# RC_Filters_MicroD.net
KiCad netlist of a schematic drawn in Altium Designer
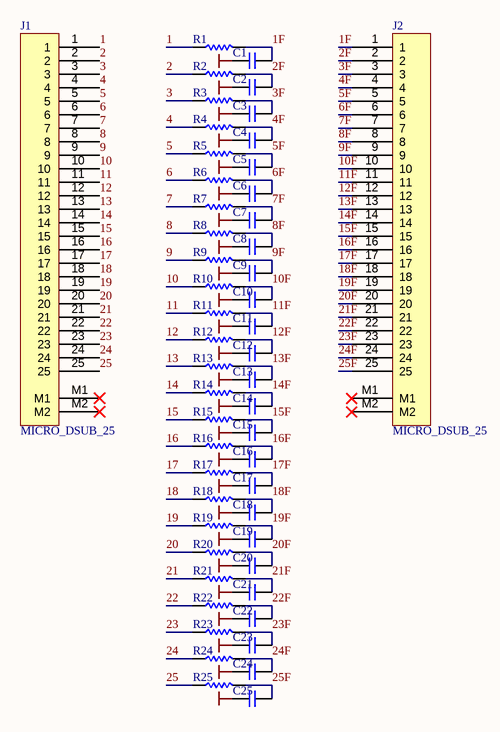
[diagram p0: RC_Filters_MicroD.SchDoc]

(export (version "E")
  (design (tool "Eeschema 10.0.6"))
  (components
    (comp (ref "C1") (value "Capacitor") (footprint "C0402") (libsource (lib "Passives") (part "Capacitor")))
    (comp (ref "C2") (value "Capacitor") (footprint "C0402") (libsource (lib "Passives") (part "Capacitor")))
    (comp (ref "C3") (value "Capacitor") (footprint "C0402") (libsource (lib "Passives") (part "Capacitor")))
    (comp (ref "C4") (value "Capacitor") (footprint "C0402") (libsource (lib "Passives") (part "Capacitor")))
    (comp (ref "C5") (value "Capacitor") (footprint "C0402") (libsource (lib "Passives") (part "Capacitor")))
    (comp (ref "C6") (value "Capacitor") (footprint "C0402") (libsource (lib "Passives") (part "Capacitor")))
    (comp (ref "C7") (value "Capacitor") (footprint "C0402") (libsource (lib "Passives") (part "Capacitor")))
    (comp (ref "C8") (value "Capacitor") (footprint "C0402") (libsource (lib "Passives") (part "Capacitor")))
    (comp (ref "C9") (value "Capacitor") (footprint "C0402") (libsource (lib "Passives") (part "Capacitor")))
    (comp (ref "C10") (value "Capacitor") (footprint "C0402") (libsource (lib "Passives") (part "Capacitor")))
    (comp (ref "C11") (value "Capacitor") (footprint "C0402") (libsource (lib "Passives") (part "Capacitor")))
    (comp (ref "C12") (value "Capacitor") (footprint "C0402") (libsource (lib "Passives") (part "Capacitor")))
    (comp (ref "C13") (value "Capacitor") (footprint "C0402") (libsource (lib "Passives") (part "Capacitor")))
    (comp (ref "C14") (value "Capacitor") (footprint "C0402") (libsource (lib "Passives") (part "Capacitor")))
    (comp (ref "C15") (value "Capacitor") (footprint "C0402") (libsource (lib "Passives") (part "Capacitor")))
    (comp (ref "C16") (value "Capacitor") (footprint "C0402") (libsource (lib "Passives") (part "Capacitor")))
    (comp (ref "C17") (value "Capacitor") (footprint "C0402") (libsource (lib "Passives") (part "Capacitor")))
    (comp (ref "C18") (value "Capacitor") (footprint "C0402") (libsource (lib "Passives") (part "Capacitor")))
    (comp (ref "C19") (value "Capacitor") (footprint "C0402") (libsource (lib "Passives") (part "Capacitor")))
    (comp (ref "C20") (value "Capacitor") (footprint "C0402") (libsource (lib "Passives") (part "Capacitor")))
    (comp (ref "C21") (value "Capacitor") (footprint "C0402") (libsource (lib "Passives") (part "Capacitor")))
    (comp (ref "C22") (value "Capacitor") (footprint "C0402") (libsource (lib "Passives") (part "Capacitor")))
    (comp (ref "C23") (value "Capacitor") (footprint "C0402") (libsource (lib "Passives") (part "Capacitor")))
    (comp (ref "C24") (value "Capacitor") (footprint "C0402") (libsource (lib "Passives") (part "Capacitor")))
    (comp (ref "C25") (value "Capacitor") (footprint "C0402") (libsource (lib "Passives") (part "Capacitor")))
    (comp (ref "J1")
      (value "MICRO_DSUB_25")
      (footprint "581-M25-113L461")
      (description "Micro D-Sub 25 pin connector")
      (libsource (lib "") (part "MICRO_DSUB_25_1"))
    )
    (comp (ref "J2")
      (value "MICRO_DSUB_25")
      (footprint "581-M25-213L461")
      (description "Micro D-Sub 25 pin connector")
      (libsource (lib "Connectors") (part "MICRO_DSUB_25"))
    )
    (comp (ref "R1") (value "Resistor") (footprint "R0402") (libsource (lib "Passives") (part "Resistor")))
    (comp (ref "R2") (value "Resistor") (footprint "R0402") (libsource (lib "Passives") (part "Resistor")))
    (comp (ref "R3") (value "Resistor") (footprint "R0402") (libsource (lib "Passives") (part "Resistor")))
    (comp (ref "R4") (value "Resistor") (footprint "R0402") (libsource (lib "Passives") (part "Resistor")))
    (comp (ref "R5") (value "Resistor") (footprint "R0402") (libsource (lib "Passives") (part "Resistor")))
    (comp (ref "R6") (value "Resistor") (footprint "R0402") (libsource (lib "Passives") (part "Resistor")))
    (comp (ref "R7") (value "Resistor") (footprint "R0402") (libsource (lib "Passives") (part "Resistor")))
    (comp (ref "R8") (value "Resistor") (footprint "R0402") (libsource (lib "Passives") (part "Resistor")))
    (comp (ref "R9") (value "Resistor") (footprint "R0402") (libsource (lib "Passives") (part "Resistor")))
    (comp (ref "R10") (value "Resistor") (footprint "R0402") (libsource (lib "Passives") (part "Resistor")))
    (comp (ref "R11") (value "Resistor") (footprint "R0402") (libsource (lib "Passives") (part "Resistor")))
    (comp (ref "R12") (value "Resistor") (footprint "R0402") (libsource (lib "Passives") (part "Resistor")))
    (comp (ref "R13") (value "Resistor") (footprint "R0402") (libsource (lib "Passives") (part "Resistor")))
    (comp (ref "R14") (value "Resistor") (footprint "R0402") (libsource (lib "Passives") (part "Resistor")))
    (comp (ref "R15") (value "Resistor") (footprint "R0402") (libsource (lib "Passives") (part "Resistor")))
    (comp (ref "R16") (value "Resistor") (footprint "R0402") (libsource (lib "Passives") (part "Resistor")))
    (comp (ref "R17") (value "Resistor") (footprint "R0402") (libsource (lib "Passives") (part "Resistor")))
    (comp (ref "R18") (value "Resistor") (footprint "R0402") (libsource (lib "Passives") (part "Resistor")))
    (comp (ref "R19") (value "Resistor") (footprint "R0402") (libsource (lib "Passives") (part "Resistor")))
    (comp (ref "R20") (value "Resistor") (footprint "R0402") (libsource (lib "Passives") (part "Resistor")))
    (comp (ref "R21") (value "Resistor") (footprint "R0402") (libsource (lib "Passives") (part "Resistor")))
    (comp (ref "R22") (value "Resistor") (footprint "R0402") (libsource (lib "Passives") (part "Resistor")))
    (comp (ref "R23") (value "Resistor") (footprint "R0402") (libsource (lib "Passives") (part "Resistor")))
    (comp (ref "R24") (value "Resistor") (footprint "R0402") (libsource (lib "Passives") (part "Resistor")))
    (comp (ref "R25") (value "Resistor") (footprint "R0402") (libsource (lib "Passives") (part "Resistor")))
  )
  (nets
    (net (code "1") (name "/1") (class "Default")
      (node (ref "J1") (pin "1") (pinfunction "1_1") (pintype "passive"))
      (node (ref "R1") (pin "0") (pinfunction "0_0") (pintype "passive"))
    )
    (net (code "2") (name "/1F") (class "Default")
      (node (ref "C1") (pin "1") (pinfunction "1_1") (pintype "passive"))
      (node (ref "J2") (pin "1") (pinfunction "1_1") (pintype "passive"))
      (node (ref "R1") (pin "1") (pinfunction "1_1") (pintype "passive"))
    )
    (net (code "3") (name "/2") (class "Default")
      (node (ref "J1") (pin "2") (pinfunction "2_2") (pintype "passive"))
      (node (ref "R2") (pin "0") (pinfunction "0_0") (pintype "passive"))
    )
    (net (code "4") (name "/2F") (class "Default")
      (node (ref "C2") (pin "1") (pinfunction "1_1") (pintype "passive"))
      (node (ref "J2") (pin "2") (pinfunction "2_2") (pintype "passive"))
      (node (ref "R2") (pin "1") (pinfunction "1_1") (pintype "passive"))
    )
    (net (code "5") (name "/3") (class "Default")
      (node (ref "J1") (pin "3") (pinfunction "3_3") (pintype "passive"))
      (node (ref "R3") (pin "0") (pinfunction "0_0") (pintype "passive"))
    )
    (net (code "6") (name "/3F") (class "Default")
      (node (ref "C3") (pin "1") (pinfunction "1_1") (pintype "passive"))
      (node (ref "J2") (pin "3") (pinfunction "3_3") (pintype "passive"))
      (node (ref "R3") (pin "1") (pinfunction "1_1") (pintype "passive"))
    )
    (net (code "7") (name "/4") (class "Default")
      (node (ref "J1") (pin "4") (pinfunction "4_4") (pintype "passive"))
      (node (ref "R4") (pin "0") (pinfunction "0_0") (pintype "passive"))
    )
    (net (code "8") (name "/4F") (class "Default")
      (node (ref "C4") (pin "1") (pinfunction "1_1") (pintype "passive"))
      (node (ref "J2") (pin "4") (pinfunction "4_4") (pintype "passive"))
      (node (ref "R4") (pin "1") (pinfunction "1_1") (pintype "passive"))
    )
    (net (code "9") (name "/5") (class "Default")
      (node (ref "J1") (pin "5") (pinfunction "5_5") (pintype "passive"))
      (node (ref "R5") (pin "0") (pinfunction "0_0") (pintype "passive"))
    )
    (net (code "10") (name "/5F") (class "Default")
      (node (ref "C5") (pin "1") (pinfunction "1_1") (pintype "passive"))
      (node (ref "J2") (pin "5") (pinfunction "5_5") (pintype "passive"))
      (node (ref "R5") (pin "1") (pinfunction "1_1") (pintype "passive"))
    )
    (net (code "11") (name "/6") (class "Default")
      (node (ref "J1") (pin "6") (pinfunction "6_6") (pintype "passive"))
      (node (ref "R6") (pin "0") (pinfunction "0_0") (pintype "passive"))
    )
    (net (code "12") (name "/6F") (class "Default")
      (node (ref "C6") (pin "1") (pinfunction "1_1") (pintype "passive"))
      (node (ref "J2") (pin "6") (pinfunction "6_6") (pintype "passive"))
      (node (ref "R6") (pin "1") (pinfunction "1_1") (pintype "passive"))
    )
    (net (code "13") (name "/7") (class "Default")
      (node (ref "J1") (pin "7") (pinfunction "7_7") (pintype "passive"))
      (node (ref "R7") (pin "0") (pinfunction "0_0") (pintype "passive"))
    )
    (net (code "14") (name "/7F") (class "Default")
      (node (ref "C7") (pin "1") (pinfunction "1_1") (pintype "passive"))
      (node (ref "J2") (pin "7") (pinfunction "7_7") (pintype "passive"))
      (node (ref "R7") (pin "1") (pinfunction "1_1") (pintype "passive"))
    )
    (net (code "15") (name "/8") (class "Default")
      (node (ref "J1") (pin "8") (pinfunction "8_8") (pintype "passive"))
      (node (ref "R8") (pin "0") (pinfunction "0_0") (pintype "passive"))
    )
    (net (code "16") (name "/8F") (class "Default")
      (node (ref "C8") (pin "1") (pinfunction "1_1") (pintype "passive"))
      (node (ref "J2") (pin "8") (pinfunction "8_8") (pintype "passive"))
      (node (ref "R8") (pin "1") (pinfunction "1_1") (pintype "passive"))
    )
    (net (code "17") (name "/9") (class "Default")
      (node (ref "J1") (pin "9") (pinfunction "9_9") (pintype "passive"))
      (node (ref "R9") (pin "0") (pinfunction "0_0") (pintype "passive"))
    )
    (net (code "18") (name "/9F") (class "Default")
      (node (ref "C9") (pin "1") (pinfunction "1_1") (pintype "passive"))
      (node (ref "J2") (pin "9") (pinfunction "9_9") (pintype "passive"))
      (node (ref "R9") (pin "1") (pinfunction "1_1") (pintype "passive"))
    )
    (net (code "19") (name "/10") (class "Default")
      (node (ref "J1") (pin "10") (pinfunction "10_10") (pintype "passive"))
      (node (ref "R10") (pin "0") (pinfunction "0_0") (pintype "passive"))
    )
    (net (code "20") (name "/10F") (class "Default")
      (node (ref "C10") (pin "1") (pinfunction "1_1") (pintype "passive"))
      (node (ref "J2") (pin "10") (pinfunction "10_10") (pintype "passive"))
      (node (ref "R10") (pin "1") (pinfunction "1_1") (pintype "passive"))
    )
    (net (code "21") (name "/11") (class "Default")
      (node (ref "J1") (pin "11") (pinfunction "11_11") (pintype "passive"))
      (node (ref "R11") (pin "0") (pinfunction "0_0") (pintype "passive"))
    )
    (net (code "22") (name "/11F") (class "Default")
      (node (ref "C11") (pin "1") (pinfunction "1_1") (pintype "passive"))
      (node (ref "J2") (pin "11") (pinfunction "11_11") (pintype "passive"))
      (node (ref "R11") (pin "1") (pinfunction "1_1") (pintype "passive"))
    )
    (net (code "23") (name "/12") (class "Default")
      (node (ref "J1") (pin "12") (pinfunction "12_12") (pintype "passive"))
      (node (ref "R12") (pin "0") (pinfunction "0_0") (pintype "passive"))
    )
    (net (code "24") (name "/12F") (class "Default")
      (node (ref "C12") (pin "1") (pinfunction "1_1") (pintype "passive"))
      (node (ref "J2") (pin "12") (pinfunction "12_12") (pintype "passive"))
      (node (ref "R12") (pin "1") (pinfunction "1_1") (pintype "passive"))
    )
    (net (code "25") (name "/13") (class "Default")
      (node (ref "J1") (pin "13") (pinfunction "13_13") (pintype "passive"))
      (node (ref "R13") (pin "0") (pinfunction "0_0") (pintype "passive"))
    )
    (net (code "26") (name "/13F") (class "Default")
      (node (ref "C13") (pin "1") (pinfunction "1_1") (pintype "passive"))
      (node (ref "J2") (pin "13") (pinfunction "13_13") (pintype "passive"))
      (node (ref "R13") (pin "1") (pinfunction "1_1") (pintype "passive"))
    )
    (net (code "27") (name "/14") (class "Default")
      (node (ref "J1") (pin "14") (pinfunction "14_14") (pintype "passive"))
      (node (ref "R14") (pin "0") (pinfunction "0_0") (pintype "passive"))
    )
    (net (code "28") (name "/14F") (class "Default")
      (node (ref "C14") (pin "1") (pinfunction "1_1") (pintype "passive"))
      (node (ref "J2") (pin "14") (pinfunction "14_14") (pintype "passive"))
      (node (ref "R14") (pin "1") (pinfunction "1_1") (pintype "passive"))
    )
    (net (code "29") (name "/15") (class "Default")
      (node (ref "J1") (pin "15") (pinfunction "15_15") (pintype "passive"))
      (node (ref "R15") (pin "0") (pinfunction "0_0") (pintype "passive"))
    )
    (net (code "30") (name "/15F") (class "Default")
      (node (ref "C15") (pin "1") (pinfunction "1_1") (pintype "passive"))
      (node (ref "J2") (pin "15") (pinfunction "15_15") (pintype "passive"))
      (node (ref "R15") (pin "1") (pinfunction "1_1") (pintype "passive"))
    )
    (net (code "31") (name "/16") (class "Default")
      (node (ref "J1") (pin "16") (pinfunction "16_16") (pintype "passive"))
      (node (ref "R16") (pin "0") (pinfunction "0_0") (pintype "passive"))
    )
    (net (code "32") (name "/16F") (class "Default")
      (node (ref "C16") (pin "1") (pinfunction "1_1") (pintype "passive"))
      (node (ref "J2") (pin "16") (pinfunction "16_16") (pintype "passive"))
      (node (ref "R16") (pin "1") (pinfunction "1_1") (pintype "passive"))
    )
    (net (code "33") (name "/17") (class "Default")
      (node (ref "J1") (pin "17") (pinfunction "17_17") (pintype "passive"))
      (node (ref "R17") (pin "0") (pinfunction "0_0") (pintype "passive"))
    )
    (net (code "34") (name "/17F") (class "Default")
      (node (ref "C17") (pin "1") (pinfunction "1_1") (pintype "passive"))
      (node (ref "J2") (pin "17") (pinfunction "17_17") (pintype "passive"))
      (node (ref "R17") (pin "1") (pinfunction "1_1") (pintype "passive"))
    )
    (net (code "35") (name "/18") (class "Default")
      (node (ref "J1") (pin "18") (pinfunction "18_18") (pintype "passive"))
      (node (ref "R18") (pin "0") (pinfunction "0_0") (pintype "passive"))
    )
    (net (code "36") (name "/18F") (class "Default")
      (node (ref "C18") (pin "1") (pinfunction "1_1") (pintype "passive"))
      (node (ref "J2") (pin "18") (pinfunction "18_18") (pintype "passive"))
      (node (ref "R18") (pin "1") (pinfunction "1_1") (pintype "passive"))
    )
    (net (code "37") (name "/19") (class "Default")
      (node (ref "J1") (pin "19") (pinfunction "19_19") (pintype "passive"))
      (node (ref "R19") (pin "0") (pinfunction "0_0") (pintype "passive"))
    )
    (net (code "38") (name "/19F") (class "Default")
      (node (ref "C19") (pin "1") (pinfunction "1_1") (pintype "passive"))
      (node (ref "J2") (pin "19") (pinfunction "19_19") (pintype "passive"))
      (node (ref "R19") (pin "1") (pinfunction "1_1") (pintype "passive"))
    )
    (net (code "39") (name "/20") (class "Default")
      (node (ref "J1") (pin "20") (pinfunction "20_20") (pintype "passive"))
      (node (ref "R20") (pin "0") (pinfunction "0_0") (pintype "passive"))
    )
    (net (code "40") (name "/20F") (class "Default")
      (node (ref "C20") (pin "1") (pinfunction "1_1") (pintype "passive"))
      (node (ref "J2") (pin "20") (pinfunction "20_20") (pintype "passive"))
      (node (ref "R20") (pin "1") (pinfunction "1_1") (pintype "passive"))
    )
    (net (code "41") (name "/21") (class "Default")
      (node (ref "J1") (pin "21") (pinfunction "21_21") (pintype "passive"))
      (node (ref "R21") (pin "0") (pinfunction "0_0") (pintype "passive"))
    )
    (net (code "42") (name "/21F") (class "Default")
      (node (ref "C21") (pin "1") (pinfunction "1_1") (pintype "passive"))
      (node (ref "J2") (pin "21") (pinfunction "21_21") (pintype "passive"))
      (node (ref "R21") (pin "1") (pinfunction "1_1") (pintype "passive"))
    )
    (net (code "43") (name "/22") (class "Default")
      (node (ref "J1") (pin "22") (pinfunction "22_22") (pintype "passive"))
      (node (ref "R22") (pin "0") (pinfunction "0_0") (pintype "passive"))
    )
    (net (code "44") (name "/22F") (class "Default")
      (node (ref "C22") (pin "1") (pinfunction "1_1") (pintype "passive"))
      (node (ref "J2") (pin "22") (pinfunction "22_22") (pintype "passive"))
      (node (ref "R22") (pin "1") (pinfunction "1_1") (pintype "passive"))
    )
    (net (code "45") (name "/23") (class "Default")
      (node (ref "J1") (pin "23") (pinfunction "23_23") (pintype "passive"))
      (node (ref "R23") (pin "0") (pinfunction "0_0") (pintype "passive"))
    )
    (net (code "46") (name "/23F") (class "Default")
      (node (ref "C23") (pin "1") (pinfunction "1_1") (pintype "passive"))
      (node (ref "J2") (pin "23") (pinfunction "23_23") (pintype "passive"))
      (node (ref "R23") (pin "1") (pinfunction "1_1") (pintype "passive"))
    )
    (net (code "47") (name "/24") (class "Default")
      (node (ref "J1") (pin "24") (pinfunction "24_24") (pintype "passive"))
      (node (ref "R24") (pin "0") (pinfunction "0_0") (pintype "passive"))
    )
    (net (code "48") (name "/24F") (class "Default")
      (node (ref "C24") (pin "1") (pinfunction "1_1") (pintype "passive"))
      (node (ref "J2") (pin "24") (pinfunction "24_24") (pintype "passive"))
      (node (ref "R24") (pin "1") (pinfunction "1_1") (pintype "passive"))
    )
    (net (code "49") (name "/25") (class "Default")
      (node (ref "J1") (pin "25") (pinfunction "25_25") (pintype "passive"))
      (node (ref "R25") (pin "0") (pinfunction "0_0") (pintype "passive"))
    )
    (net (code "50") (name "/25F") (class "Default")
      (node (ref "C25") (pin "1") (pinfunction "1_1") (pintype "passive"))
      (node (ref "J2") (pin "25") (pinfunction "25_25") (pintype "passive"))
      (node (ref "R25") (pin "1") (pinfunction "1_1") (pintype "passive"))
    )
    (net (code "51") (name "COM") (class "Default")
      (node (ref "C1") (pin "0") (pinfunction "0_0") (pintype "passive"))
      (node (ref "C10") (pin "0") (pinfunction "0_0") (pintype "passive"))
      (node (ref "C11") (pin "0") (pinfunction "0_0") (pintype "passive"))
      (node (ref "C12") (pin "0") (pinfunction "0_0") (pintype "passive"))
      (node (ref "C13") (pin "0") (pinfunction "0_0") (pintype "passive"))
      (node (ref "C14") (pin "0") (pinfunction "0_0") (pintype "passive"))
      (node (ref "C15") (pin "0") (pinfunction "0_0") (pintype "passive"))
      (node (ref "C16") (pin "0") (pinfunction "0_0") (pintype "passive"))
      (node (ref "C17") (pin "0") (pinfunction "0_0") (pintype "passive"))
      (node (ref "C18") (pin "0") (pinfunction "0_0") (pintype "passive"))
      (node (ref "C19") (pin "0") (pinfunction "0_0") (pintype "passive"))
      (node (ref "C2") (pin "0") (pinfunction "0_0") (pintype "passive"))
      (node (ref "C20") (pin "0") (pinfunction "0_0") (pintype "passive"))
      (node (ref "C21") (pin "0") (pinfunction "0_0") (pintype "passive"))
      (node (ref "C22") (pin "0") (pinfunction "0_0") (pintype "passive"))
      (node (ref "C23") (pin "0") (pinfunction "0_0") (pintype "passive"))
      (node (ref "C24") (pin "0") (pinfunction "0_0") (pintype "passive"))
      (node (ref "C25") (pin "0") (pinfunction "0_0") (pintype "passive"))
      (node (ref "C3") (pin "0") (pinfunction "0_0") (pintype "passive"))
      (node (ref "C4") (pin "0") (pinfunction "0_0") (pintype "passive"))
      (node (ref "C5") (pin "0") (pinfunction "0_0") (pintype "passive"))
      (node (ref "C6") (pin "0") (pinfunction "0_0") (pintype "passive"))
      (node (ref "C7") (pin "0") (pinfunction "0_0") (pintype "passive"))
      (node (ref "C8") (pin "0") (pinfunction "0_0") (pintype "passive"))
      (node (ref "C9") (pin "0") (pinfunction "0_0") (pintype "passive"))
    )
    (net (code "52") (name "unconnected-(J1-PadM1)") (class "Default")
      (node (ref "J1") (pin "M1") (pinfunction "M1_M1") (pintype "passive+no_connect"))
    )
    (net (code "53") (name "unconnected-(J1-PadM2)") (class "Default")
      (node (ref "J1") (pin "M2") (pinfunction "M2_M2") (pintype "passive+no_connect"))
    )
    (net (code "54") (name "unconnected-(J2-PadM1)") (class "Default")
      (node (ref "J2") (pin "M1") (pinfunction "M1_M1") (pintype "passive+no_connect"))
    )
    (net (code "55") (name "unconnected-(J2-PadM2)") (class "Default")
      (node (ref "J2") (pin "M2") (pinfunction "M2_M2") (pintype "passive+no_connect"))
    )
  )
)
